# L3DCube_16LED_Rev1.net
KiCad netlist of a schematic drawn in EAGLE
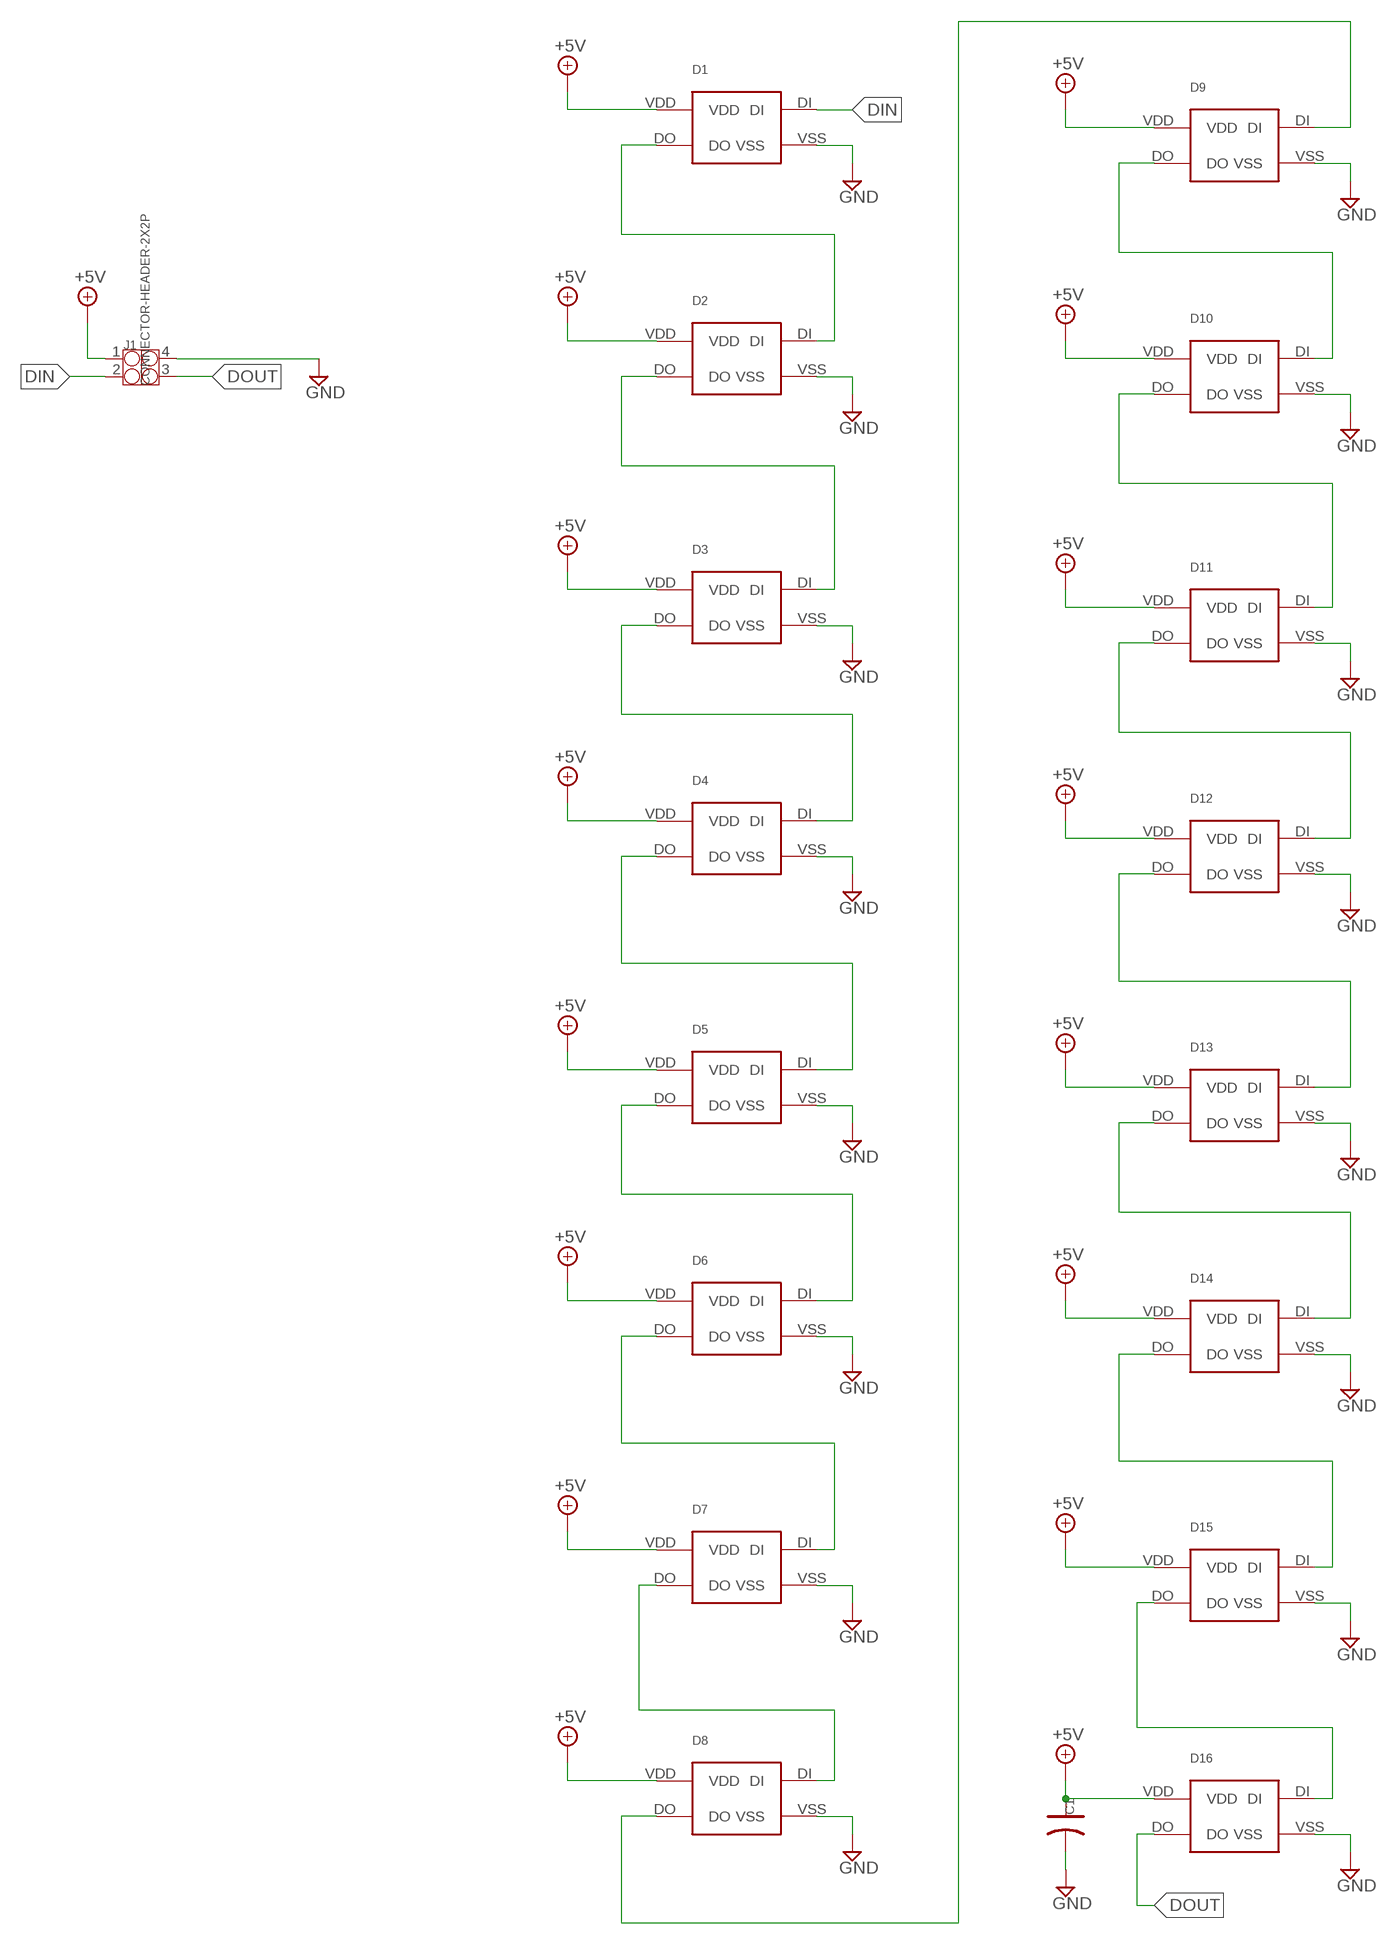
[diagram p0: schematic, sheet 1]

(export (version "E")
  (design (tool "Eeschema 10.0.6"))
  (components
    (comp (ref "C1")
      (value "C-POLAR-A")
      (footprint "eagle-import:AVX-A")
      (libsource (lib "eagle-import") (part "C-POLAR-A"))
    )
    (comp (ref "D1")
      (value "WS2812B")
      (footprint "eagle-import:WS2812B")
      (libsource (lib "eagle-import") (part "WS2812B"))
    )
    (comp (ref "D2")
      (value "WS2812B")
      (footprint "eagle-import:WS2812B")
      (libsource (lib "eagle-import") (part "WS2812B"))
    )
    (comp (ref "D3")
      (value "WS2812B")
      (footprint "eagle-import:WS2812B")
      (libsource (lib "eagle-import") (part "WS2812B"))
    )
    (comp (ref "D4")
      (value "WS2812B")
      (footprint "eagle-import:WS2812B")
      (libsource (lib "eagle-import") (part "WS2812B"))
    )
    (comp (ref "D5")
      (value "WS2812B")
      (footprint "eagle-import:WS2812B")
      (libsource (lib "eagle-import") (part "WS2812B"))
    )
    (comp (ref "D6")
      (value "WS2812B")
      (footprint "eagle-import:WS2812B")
      (libsource (lib "eagle-import") (part "WS2812B"))
    )
    (comp (ref "D7")
      (value "WS2812B")
      (footprint "eagle-import:WS2812B")
      (libsource (lib "eagle-import") (part "WS2812B"))
    )
    (comp (ref "D8")
      (value "WS2812B")
      (footprint "eagle-import:WS2812B")
      (libsource (lib "eagle-import") (part "WS2812B"))
    )
    (comp (ref "D9")
      (value "WS2812B")
      (footprint "eagle-import:WS2812B")
      (libsource (lib "eagle-import") (part "WS2812B"))
    )
    (comp (ref "D10")
      (value "WS2812B")
      (footprint "eagle-import:WS2812B")
      (libsource (lib "eagle-import") (part "WS2812B"))
    )
    (comp (ref "D11")
      (value "WS2812B")
      (footprint "eagle-import:WS2812B")
      (libsource (lib "eagle-import") (part "WS2812B"))
    )
    (comp (ref "D12")
      (value "WS2812B")
      (footprint "eagle-import:WS2812B")
      (libsource (lib "eagle-import") (part "WS2812B"))
    )
    (comp (ref "D13")
      (value "WS2812B")
      (footprint "eagle-import:WS2812B")
      (libsource (lib "eagle-import") (part "WS2812B"))
    )
    (comp (ref "D14")
      (value "WS2812B")
      (footprint "eagle-import:WS2812B")
      (libsource (lib "eagle-import") (part "WS2812B"))
    )
    (comp (ref "D15")
      (value "WS2812B")
      (footprint "eagle-import:WS2812B")
      (libsource (lib "eagle-import") (part "WS2812B"))
    )
    (comp (ref "D16")
      (value "WS2812B")
      (footprint "eagle-import:WS2812B")
      (libsource (lib "eagle-import") (part "WS2812B"))
    )
    (comp (ref "J1")
      (value "CONNECTOR-HEADER-2X2P")
      (footprint "eagle-import:2X2P-2.54")
      (libsource (lib "eagle-import") (part "CONNECTOR-HEADER-2X2P"))
    )
  )
  (nets
    (net (code "1") (name "+5V") (class "Default")
      (node (ref "C1") (pin "+") (pinfunction "1_+") (pintype "bidirectional"))
      (node (ref "D1") (pin "VDD") (pinfunction "VDD_VDD") (pintype "bidirectional"))
      (node (ref "D10") (pin "VDD") (pinfunction "VDD_VDD") (pintype "bidirectional"))
      (node (ref "D11") (pin "VDD") (pinfunction "VDD_VDD") (pintype "bidirectional"))
      (node (ref "D12") (pin "VDD") (pinfunction "VDD_VDD") (pintype "bidirectional"))
      (node (ref "D13") (pin "VDD") (pinfunction "VDD_VDD") (pintype "bidirectional"))
      (node (ref "D14") (pin "VDD") (pinfunction "VDD_VDD") (pintype "bidirectional"))
      (node (ref "D15") (pin "VDD") (pinfunction "VDD_VDD") (pintype "bidirectional"))
      (node (ref "D16") (pin "VDD") (pinfunction "VDD_VDD") (pintype "bidirectional"))
      (node (ref "D2") (pin "VDD") (pinfunction "VDD_VDD") (pintype "bidirectional"))
      (node (ref "D3") (pin "VDD") (pinfunction "VDD_VDD") (pintype "bidirectional"))
      (node (ref "D4") (pin "VDD") (pinfunction "VDD_VDD") (pintype "bidirectional"))
      (node (ref "D5") (pin "VDD") (pinfunction "VDD_VDD") (pintype "bidirectional"))
      (node (ref "D6") (pin "VDD") (pinfunction "VDD_VDD") (pintype "bidirectional"))
      (node (ref "D7") (pin "VDD") (pinfunction "VDD_VDD") (pintype "bidirectional"))
      (node (ref "D8") (pin "VDD") (pinfunction "VDD_VDD") (pintype "bidirectional"))
      (node (ref "D9") (pin "VDD") (pinfunction "VDD_VDD") (pintype "bidirectional"))
      (node (ref "J1") (pin "1") (pinfunction "1_1") (pintype "bidirectional"))
    )
    (net (code "2") (name "DIN") (class "Default")
      (node (ref "D1") (pin "DI") (pinfunction "DI_DI") (pintype "bidirectional"))
      (node (ref "J1") (pin "2") (pinfunction "2_2") (pintype "bidirectional"))
    )
    (net (code "3") (name "DOUT") (class "Default")
      (node (ref "D16") (pin "DO") (pinfunction "DO_DO") (pintype "bidirectional"))
      (node (ref "J1") (pin "3") (pinfunction "3_3") (pintype "bidirectional"))
    )
    (net (code "4") (name "GND") (class "Default")
      (node (ref "C1") (pin "-") (pinfunction "2_-") (pintype "bidirectional"))
      (node (ref "D1") (pin "VSS") (pinfunction "VSS_VSS") (pintype "bidirectional"))
      (node (ref "D10") (pin "VSS") (pinfunction "VSS_VSS") (pintype "bidirectional"))
      (node (ref "D11") (pin "VSS") (pinfunction "VSS_VSS") (pintype "bidirectional"))
      (node (ref "D12") (pin "VSS") (pinfunction "VSS_VSS") (pintype "bidirectional"))
      (node (ref "D13") (pin "VSS") (pinfunction "VSS_VSS") (pintype "bidirectional"))
      (node (ref "D14") (pin "VSS") (pinfunction "VSS_VSS") (pintype "bidirectional"))
      (node (ref "D15") (pin "VSS") (pinfunction "VSS_VSS") (pintype "bidirectional"))
      (node (ref "D16") (pin "VSS") (pinfunction "VSS_VSS") (pintype "bidirectional"))
      (node (ref "D2") (pin "VSS") (pinfunction "VSS_VSS") (pintype "bidirectional"))
      (node (ref "D3") (pin "VSS") (pinfunction "VSS_VSS") (pintype "bidirectional"))
      (node (ref "D4") (pin "VSS") (pinfunction "VSS_VSS") (pintype "bidirectional"))
      (node (ref "D5") (pin "VSS") (pinfunction "VSS_VSS") (pintype "bidirectional"))
      (node (ref "D6") (pin "VSS") (pinfunction "VSS_VSS") (pintype "bidirectional"))
      (node (ref "D7") (pin "VSS") (pinfunction "VSS_VSS") (pintype "bidirectional"))
      (node (ref "D8") (pin "VSS") (pinfunction "VSS_VSS") (pintype "bidirectional"))
      (node (ref "D9") (pin "VSS") (pinfunction "VSS_VSS") (pintype "bidirectional"))
      (node (ref "J1") (pin "4") (pinfunction "4_4") (pintype "bidirectional"))
    )
    (net (code "5") (name "Net-(D1-PadDO)") (class "Default")
      (node (ref "D1") (pin "DO") (pinfunction "DO_DO") (pintype "bidirectional"))
      (node (ref "D2") (pin "DI") (pinfunction "DI_DI") (pintype "bidirectional"))
    )
    (net (code "6") (name "Net-(D2-PadDO)") (class "Default")
      (node (ref "D2") (pin "DO") (pinfunction "DO_DO") (pintype "bidirectional"))
      (node (ref "D3") (pin "DI") (pinfunction "DI_DI") (pintype "bidirectional"))
    )
    (net (code "7") (name "Net-(D3-PadDO)") (class "Default")
      (node (ref "D3") (pin "DO") (pinfunction "DO_DO") (pintype "bidirectional"))
      (node (ref "D4") (pin "DI") (pinfunction "DI_DI") (pintype "bidirectional"))
    )
    (net (code "8") (name "Net-(D4-PadDO)") (class "Default")
      (node (ref "D4") (pin "DO") (pinfunction "DO_DO") (pintype "bidirectional"))
      (node (ref "D5") (pin "DI") (pinfunction "DI_DI") (pintype "bidirectional"))
    )
    (net (code "9") (name "Net-(D5-PadDO)") (class "Default")
      (node (ref "D5") (pin "DO") (pinfunction "DO_DO") (pintype "bidirectional"))
      (node (ref "D6") (pin "DI") (pinfunction "DI_DI") (pintype "bidirectional"))
    )
    (net (code "10") (name "Net-(D6-PadDO)") (class "Default")
      (node (ref "D6") (pin "DO") (pinfunction "DO_DO") (pintype "bidirectional"))
      (node (ref "D7") (pin "DI") (pinfunction "DI_DI") (pintype "bidirectional"))
    )
    (net (code "11") (name "Net-(D7-PadDO)") (class "Default")
      (node (ref "D7") (pin "DO") (pinfunction "DO_DO") (pintype "bidirectional"))
      (node (ref "D8") (pin "DI") (pinfunction "DI_DI") (pintype "bidirectional"))
    )
    (net (code "12") (name "Net-(D8-PadDO)") (class "Default")
      (node (ref "D8") (pin "DO") (pinfunction "DO_DO") (pintype "bidirectional"))
      (node (ref "D9") (pin "DI") (pinfunction "DI_DI") (pintype "bidirectional"))
    )
    (net (code "13") (name "Net-(D10-PadDI)") (class "Default")
      (node (ref "D10") (pin "DI") (pinfunction "DI_DI") (pintype "bidirectional"))
      (node (ref "D9") (pin "DO") (pinfunction "DO_DO") (pintype "bidirectional"))
    )
    (net (code "14") (name "Net-(D10-PadDO)") (class "Default")
      (node (ref "D10") (pin "DO") (pinfunction "DO_DO") (pintype "bidirectional"))
      (node (ref "D11") (pin "DI") (pinfunction "DI_DI") (pintype "bidirectional"))
    )
    (net (code "15") (name "Net-(D11-PadDO)") (class "Default")
      (node (ref "D11") (pin "DO") (pinfunction "DO_DO") (pintype "bidirectional"))
      (node (ref "D12") (pin "DI") (pinfunction "DI_DI") (pintype "bidirectional"))
    )
    (net (code "16") (name "Net-(D12-PadDO)") (class "Default")
      (node (ref "D12") (pin "DO") (pinfunction "DO_DO") (pintype "bidirectional"))
      (node (ref "D13") (pin "DI") (pinfunction "DI_DI") (pintype "bidirectional"))
    )
    (net (code "17") (name "Net-(D13-PadDO)") (class "Default")
      (node (ref "D13") (pin "DO") (pinfunction "DO_DO") (pintype "bidirectional"))
      (node (ref "D14") (pin "DI") (pinfunction "DI_DI") (pintype "bidirectional"))
    )
    (net (code "18") (name "Net-(D14-PadDO)") (class "Default")
      (node (ref "D14") (pin "DO") (pinfunction "DO_DO") (pintype "bidirectional"))
      (node (ref "D15") (pin "DI") (pinfunction "DI_DI") (pintype "bidirectional"))
    )
    (net (code "19") (name "Net-(D15-PadDO)") (class "Default")
      (node (ref "D15") (pin "DO") (pinfunction "DO_DO") (pintype "bidirectional"))
      (node (ref "D16") (pin "DI") (pinfunction "DI_DI") (pintype "bidirectional"))
    )
  )
)
